# USB_Host.net
KiCad netlist of a schematic drawn in EAGLE
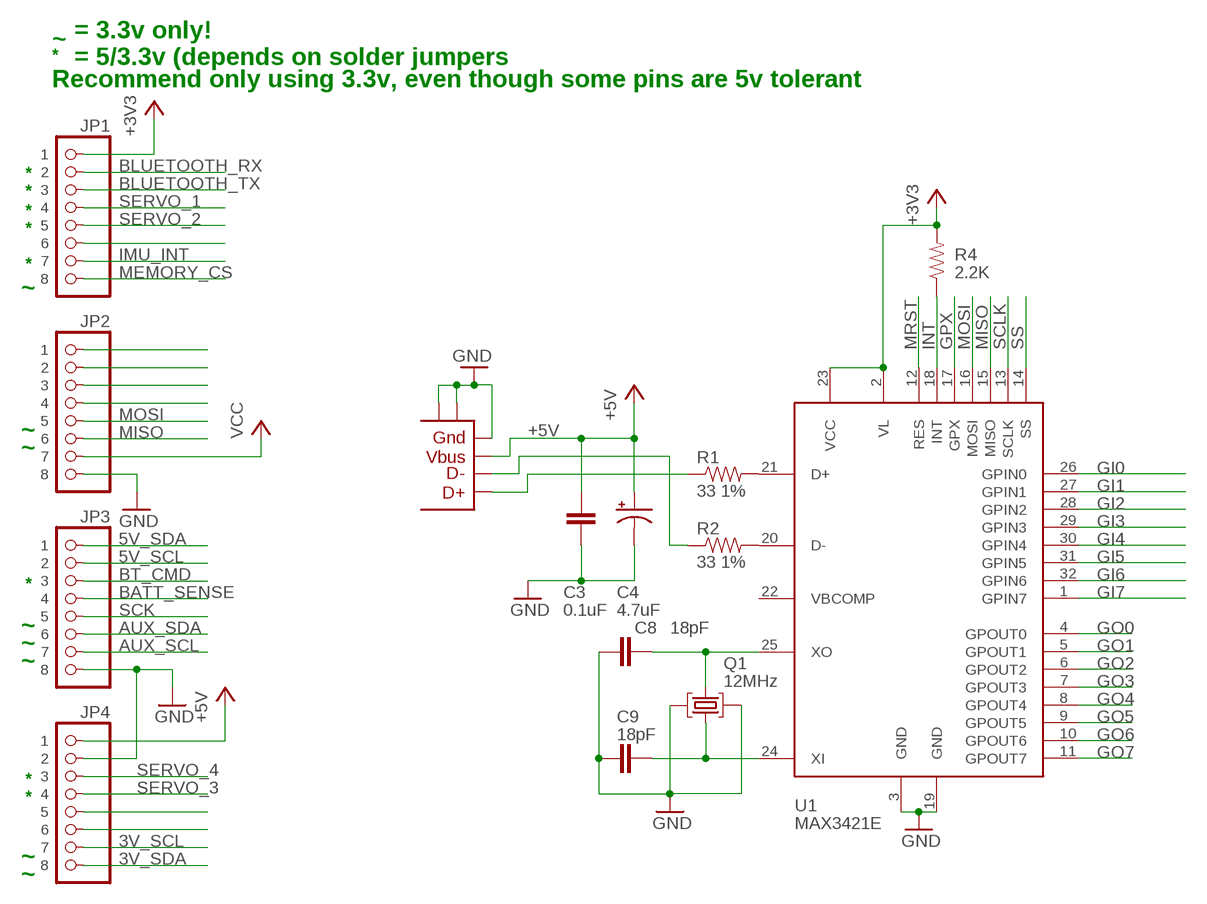
[diagram p0: schematic, sheet 1]

(export (version "E")
  (design (tool "Eeschema 10.0.6"))
  (components
    (comp (ref "C3")
      (value "0.1uF")
      (footprint "eagle-import:0603")
      (libsource (lib "eagle-import") (part "CAP0603"))
    )
    (comp (ref "C4")
      (value "4.7uF")
      (footprint "eagle-import:EIA3216")
      (libsource (lib "eagle-import") (part "CAP_POL1206"))
    )
    (comp (ref "C8")
      (value "18pF")
      (footprint "eagle-import:0603")
      (libsource (lib "eagle-import") (part "CAP0603"))
    )
    (comp (ref "C9")
      (value "18pF")
      (footprint "eagle-import:0603")
      (libsource (lib "eagle-import") (part "CAP0603"))
    )
    (comp (ref "JP1")
      (value "8-PIN_HEADER")
      (footprint "eagle-import:8-PIN_RECEPTACLE_LOCK_NO-SS")
      (libsource (lib "eagle-import") (part "8-PIN_HEADER"))
    )
    (comp (ref "JP2")
      (value "8-PIN_HEADER")
      (footprint "eagle-import:8-PIN_RECEPTACLE_LOCK_NO-SS")
      (libsource (lib "eagle-import") (part "8-PIN_HEADER"))
    )
    (comp (ref "JP3")
      (value "8-PIN_HEADER")
      (footprint "eagle-import:8-PIN_RECEPTACLE_LOCK_NO-SS")
      (libsource (lib "eagle-import") (part "8-PIN_HEADER"))
    )
    (comp (ref "JP4")
      (value "8-PIN_HEADER")
      (footprint "eagle-import:8-PIN_RECEPTACLE_LOCK_NO-SS")
      (libsource (lib "eagle-import") (part "8-PIN_HEADER"))
    )
    (comp (ref "Q1")
      (value "12MHz")
      (footprint "eagle-import:CRYSTAL-SMD-5X3")
      (libsource (lib "eagle-import") (part "CRYSTAL_SH"))
    )
    (comp (ref "R1")
      (value "33 1%")
      (footprint "eagle-import:0603")
      (libsource (lib "eagle-import") (part "RESISTOR0603"))
    )
    (comp (ref "R2")
      (value "33 1%")
      (footprint "eagle-import:0603")
      (libsource (lib "eagle-import") (part "RESISTOR0603"))
    )
    (comp (ref "R4")
      (value "2.2K")
      (footprint "eagle-import:0603")
      (libsource (lib "eagle-import") (part "RESISTOR0603"))
    )
    (comp (ref "U$1")
      (value "USB_SOCKETTYPE-A")
      (footprint "eagle-import:USB_SOCKET")
      (fields (field (name "PART#") "USB-A1HSW6"))
      (libsource (lib "eagle-import") (part "USB_SOCKETTYPE-A"))
    )
    (comp (ref "U1")
      (value "MAX3421E")
      (footprint "eagle-import:TQFP32_8MIL")
      (libsource (lib "eagle-import") (part "MAX3421E"))
    )
  )
  (nets
    (net (code "1") (name "+3V3") (class "Default")
      (node (ref "JP1") (pin "P$1") (pinfunction "1_P$1") (pintype "passive"))
      (node (ref "R4") (pin "2") (pinfunction "2_2") (pintype "passive"))
      (node (ref "U1") (pin "2") (pinfunction "VL_2") (pintype "input"))
      (node (ref "U1") (pin "23") (pinfunction "VCC_23") (pintype "power_in"))
    )
    (net (code "2") (name "+5V") (class "Default")
      (node (ref "C3") (pin "1") (pinfunction "1_1") (pintype "passive"))
      (node (ref "C4") (pin "A") (pinfunction "+_A") (pintype "passive"))
      (node (ref "JP4") (pin "P$1") (pinfunction "1_P$1") (pintype "passive"))
      (node (ref "U$1") (pin "P$1") (pinfunction "VBUS_P$1") (pintype "bidirectional"))
    )
    (net (code "3") (name "/3V_SCL") (class "Default")
      (node (ref "JP4") (pin "P$7") (pinfunction "7_P$7") (pintype "passive"))
    )
    (net (code "4") (name "/3V_SDA") (class "Default")
      (node (ref "JP4") (pin "P$8") (pinfunction "8_P$8") (pintype "passive"))
    )
    (net (code "5") (name "/5V_SCL") (class "Default")
      (node (ref "JP3") (pin "P$2") (pinfunction "2_P$2") (pintype "passive"))
    )
    (net (code "6") (name "/5V_SDA") (class "Default")
      (node (ref "JP3") (pin "P$1") (pinfunction "1_P$1") (pintype "passive"))
    )
    (net (code "7") (name "/AUX_SCL") (class "Default")
      (node (ref "JP3") (pin "P$7") (pinfunction "7_P$7") (pintype "passive"))
    )
    (net (code "8") (name "/AUX_SDA") (class "Default")
      (node (ref "JP3") (pin "P$6") (pinfunction "6_P$6") (pintype "passive"))
    )
    (net (code "9") (name "/BATT_SENSE") (class "Default")
      (node (ref "JP3") (pin "P$4") (pinfunction "4_P$4") (pintype "passive"))
    )
    (net (code "10") (name "/BLUETOOTH_RX") (class "Default")
      (node (ref "JP1") (pin "P$2") (pinfunction "2_P$2") (pintype "passive"))
    )
    (net (code "11") (name "/BLUETOOTH_TX") (class "Default")
      (node (ref "JP1") (pin "P$3") (pinfunction "3_P$3") (pintype "passive"))
    )
    (net (code "12") (name "/BT_CMD") (class "Default")
      (node (ref "JP3") (pin "P$3") (pinfunction "3_P$3") (pintype "passive"))
    )
    (net (code "13") (name "/GI0") (class "Default")
      (node (ref "U1") (pin "26") (pinfunction "GPIN0_26") (pintype "input"))
    )
    (net (code "14") (name "/GI1") (class "Default")
      (node (ref "U1") (pin "27") (pinfunction "GPIN1_27") (pintype "input"))
    )
    (net (code "15") (name "/GI2") (class "Default")
      (node (ref "U1") (pin "28") (pinfunction "GPIN2_28") (pintype "input"))
    )
    (net (code "16") (name "/GI3") (class "Default")
      (node (ref "U1") (pin "29") (pinfunction "GPIN3_29") (pintype "input"))
    )
    (net (code "17") (name "/GI4") (class "Default")
      (node (ref "U1") (pin "30") (pinfunction "GPIN4_30") (pintype "input"))
    )
    (net (code "18") (name "/GI5") (class "Default")
      (node (ref "U1") (pin "31") (pinfunction "GPIN5_31") (pintype "input"))
    )
    (net (code "19") (name "/GI6") (class "Default")
      (node (ref "U1") (pin "32") (pinfunction "GPIN6_32") (pintype "input"))
    )
    (net (code "20") (name "/GI7") (class "Default")
      (node (ref "U1") (pin "1") (pinfunction "GPIN7_1") (pintype "input"))
    )
    (net (code "21") (name "/GO0") (class "Default")
      (node (ref "U1") (pin "4") (pinfunction "GPOUT0_4") (pintype "output"))
    )
    (net (code "22") (name "/GO1") (class "Default")
      (node (ref "U1") (pin "5") (pinfunction "GPOUT1_5") (pintype "output"))
    )
    (net (code "23") (name "/GO2") (class "Default")
      (node (ref "U1") (pin "6") (pinfunction "GPOUT2_6") (pintype "output"))
    )
    (net (code "24") (name "/GO3") (class "Default")
      (node (ref "U1") (pin "7") (pinfunction "GPOUT3_7") (pintype "output"))
    )
    (net (code "25") (name "/GO4") (class "Default")
      (node (ref "U1") (pin "8") (pinfunction "GPOUT4_8") (pintype "output"))
    )
    (net (code "26") (name "/GO5") (class "Default")
      (node (ref "U1") (pin "9") (pinfunction "GPOUT5_9") (pintype "output"))
    )
    (net (code "27") (name "/GO6") (class "Default")
      (node (ref "U1") (pin "10") (pinfunction "GPOUT6_10") (pintype "output"))
    )
    (net (code "28") (name "/GO7") (class "Default")
      (node (ref "U1") (pin "11") (pinfunction "GPOUT7_11") (pintype "output"))
    )
    (net (code "29") (name "/GPX") (class "Default")
      (node (ref "U1") (pin "17") (pinfunction "GPX_17") (pintype "output"))
    )
    (net (code "30") (name "/IMU_INT") (class "Default")
      (node (ref "JP1") (pin "P$7") (pinfunction "7_P$7") (pintype "passive"))
    )
    (net (code "31") (name "/INT") (class "Default")
      (node (ref "R4") (pin "1") (pinfunction "1_1") (pintype "passive"))
      (node (ref "U1") (pin "18") (pinfunction "INT_18") (pintype "output"))
    )
    (net (code "32") (name "/MEMORY_CS") (class "Default")
      (node (ref "JP1") (pin "P$8") (pinfunction "8_P$8") (pintype "passive"))
    )
    (net (code "33") (name "/MISO") (class "Default")
      (node (ref "JP2") (pin "P$6") (pinfunction "6_P$6") (pintype "passive"))
      (node (ref "U1") (pin "15") (pinfunction "MISO_15") (pintype "output"))
    )
    (net (code "34") (name "/MOSI") (class "Default")
      (node (ref "JP2") (pin "P$5") (pinfunction "5_P$5") (pintype "passive"))
      (node (ref "U1") (pin "16") (pinfunction "MOSI_16") (pintype "input"))
    )
    (net (code "35") (name "/MRST") (class "Default")
      (node (ref "U1") (pin "12") (pinfunction "RES_12") (pintype "input"))
    )
    (net (code "36") (name "/SCK") (class "Default")
      (node (ref "JP3") (pin "P$5") (pinfunction "5_P$5") (pintype "passive"))
    )
    (net (code "37") (name "/SCLK") (class "Default")
      (node (ref "U1") (pin "13") (pinfunction "SCLK_13") (pintype "input"))
    )
    (net (code "38") (name "/SERVO_1") (class "Default")
      (node (ref "JP1") (pin "P$4") (pinfunction "4_P$4") (pintype "passive"))
    )
    (net (code "39") (name "/SERVO_2") (class "Default")
      (node (ref "JP1") (pin "P$5") (pinfunction "5_P$5") (pintype "passive"))
    )
    (net (code "40") (name "/SERVO_3") (class "Default")
      (node (ref "JP4") (pin "P$4") (pinfunction "4_P$4") (pintype "passive"))
    )
    (net (code "41") (name "/SERVO_4") (class "Default")
      (node (ref "JP4") (pin "P$3") (pinfunction "3_P$3") (pintype "passive"))
    )
    (net (code "42") (name "/SS") (class "Default")
      (node (ref "U1") (pin "14") (pinfunction "SS_14") (pintype "input"))
    )
    (net (code "43") (name "GND") (class "Default")
      (node (ref "C3") (pin "2") (pinfunction "2_2") (pintype "passive"))
      (node (ref "C4") (pin "C") (pinfunction "-_C") (pintype "passive"))
      (node (ref "C8") (pin "1") (pinfunction "1_1") (pintype "passive"))
      (node (ref "C9") (pin "1") (pinfunction "1_1") (pintype "passive"))
      (node (ref "JP2") (pin "P$8") (pinfunction "8_P$8") (pintype "passive"))
      (node (ref "JP3") (pin "P$8") (pinfunction "8_P$8") (pintype "passive"))
      (node (ref "JP4") (pin "P$2") (pinfunction "2_P$2") (pintype "passive"))
      (node (ref "Q1") (pin "2") (pinfunction "3_2") (pintype "passive"))
      (node (ref "Q1") (pin "4") (pinfunction "4_4") (pintype "passive"))
      (node (ref "U$1") (pin "P$4") (pinfunction "GND_P$4") (pintype "bidirectional"))
      (node (ref "U$1") (pin "P$5") (pinfunction "P$1_P$5") (pintype "bidirectional"))
      (node (ref "U$1") (pin "P$6") (pinfunction "P$2_P$6") (pintype "bidirectional"))
      (node (ref "U1") (pin "19") (pinfunction "GND_19") (pintype "power_in"))
      (node (ref "U1") (pin "3") (pinfunction "GND_3") (pintype "power_in"))
    )
    (net (code "44") (name "Net-(Q1-2)") (class "Default")
      (node (ref "C8") (pin "2") (pinfunction "2_2") (pintype "passive"))
      (node (ref "Q1") (pin "3") (pinfunction "2_3") (pintype "passive"))
      (node (ref "U1") (pin "25") (pinfunction "XO_25") (pintype "output"))
    )
    (net (code "45") (name "Net-(U$1-D+)") (class "Default")
      (node (ref "R1") (pin "1") (pinfunction "1_1") (pintype "passive"))
      (node (ref "U$1") (pin "P$3") (pinfunction "D+_P$3") (pintype "bidirectional"))
    )
    (net (code "46") (name "Net-(U$1-D-)") (class "Default")
      (node (ref "R2") (pin "1") (pinfunction "1_1") (pintype "passive"))
      (node (ref "U$1") (pin "P$2") (pinfunction "D-_P$2") (pintype "bidirectional"))
    )
    (net (code "47") (name "Net-(U1-D+)") (class "Default")
      (node (ref "R1") (pin "2") (pinfunction "2_2") (pintype "passive"))
      (node (ref "U1") (pin "21") (pinfunction "D+_21") (pintype "bidirectional"))
    )
    (net (code "48") (name "Net-(U1-D-)") (class "Default")
      (node (ref "R2") (pin "2") (pinfunction "2_2") (pintype "passive"))
      (node (ref "U1") (pin "20") (pinfunction "D-_20") (pintype "bidirectional"))
    )
    (net (code "49") (name "Net-(U1-XI)") (class "Default")
      (node (ref "C9") (pin "2") (pinfunction "2_2") (pintype "passive"))
      (node (ref "Q1") (pin "1") (pinfunction "1_1") (pintype "passive"))
      (node (ref "U1") (pin "24") (pinfunction "XI_24") (pintype "input"))
    )
    (net (code "50") (name "VCC") (class "Default")
      (node (ref "JP2") (pin "P$7") (pinfunction "7_P$7") (pintype "passive"))
    )
    (net (code "51") (name "unconnected-(JP1-6-PadP$6)") (class "Default")
      (node (ref "JP1") (pin "P$6") (pinfunction "6_P$6") (pintype "passive"))
    )
    (net (code "52") (name "unconnected-(JP2-1-PadP$1)") (class "Default")
      (node (ref "JP2") (pin "P$1") (pinfunction "1_P$1") (pintype "passive"))
    )
    (net (code "53") (name "unconnected-(JP2-2-PadP$2)") (class "Default")
      (node (ref "JP2") (pin "P$2") (pinfunction "2_P$2") (pintype "passive"))
    )
    (net (code "54") (name "unconnected-(JP2-3-PadP$3)") (class "Default")
      (node (ref "JP2") (pin "P$3") (pinfunction "3_P$3") (pintype "passive"))
    )
    (net (code "55") (name "unconnected-(JP2-4-PadP$4)") (class "Default")
      (node (ref "JP2") (pin "P$4") (pinfunction "4_P$4") (pintype "passive"))
    )
    (net (code "56") (name "unconnected-(JP4-5-PadP$5)") (class "Default")
      (node (ref "JP4") (pin "P$5") (pinfunction "5_P$5") (pintype "passive"))
    )
    (net (code "57") (name "unconnected-(JP4-6-PadP$6)") (class "Default")
      (node (ref "JP4") (pin "P$6") (pinfunction "6_P$6") (pintype "passive"))
    )
    (net (code "58") (name "unconnected-(U1-VBCOMP-Pad22)") (class "Default")
      (node (ref "U1") (pin "22") (pinfunction "VBCOMP_22") (pintype "input"))
    )
  )
)
